# IRIO.net
KiCad netlist of a schematic drawn in EAGLE
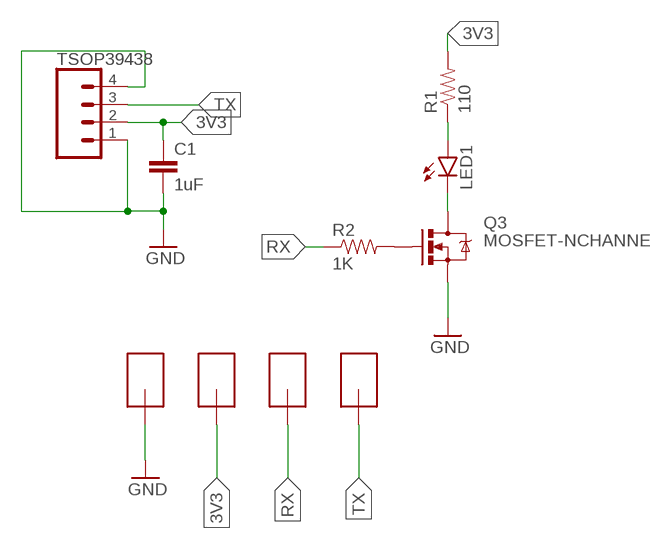
[diagram p0: schematic, sheet 1]

(export (version "E")
  (design (tool "Eeschema 10.0.6"))
  (components
    (comp (ref "C1")
      (value "1uF")
      (footprint "eagle-import:0805")
      (libsource (lib "eagle-import") (part "CAP0805"))
    )
    (comp (ref "LED1")
      (value "LED5MM")
      (footprint "eagle-import:LED5MM")
      (libsource (lib "eagle-import") (part "LED5MM"))
    )
    (comp (ref "Q3")
      (value "MOSFET-NCHANNEL")
      (footprint "eagle-import:SOT23-3")
      (libsource (lib "eagle-import") (part "MOSFET-NCHANNELAO3404A"))
    )
    (comp (ref "R1")
      (value "110")
      (footprint "eagle-import:0805")
      (libsource (lib "eagle-import") (part "RESISTOR0805-RES"))
    )
    (comp (ref "R2")
      (value "1K")
      (footprint "eagle-import:0805")
      (libsource (lib "eagle-import") (part "RESISTOR0805-RES"))
    )
    (comp (ref "TSOP39438")
      (value "CONN_041.27MM")
      (footprint "eagle-import:1X04_1.27MM")
      (libsource (lib "eagle-import") (part "CONN_041.27MM"))
    )
    (comp (ref "U$1")
      (value "SMD-PAD1SMD-PAD80X32")
      (footprint "eagle-import:SMD-PAD6")
      (libsource (lib "eagle-import") (part "SMD-PAD1SMD-PAD80X32"))
    )
    (comp (ref "U$2")
      (value "SMD-PAD1SMD-PAD80X32")
      (footprint "eagle-import:SMD-PAD6")
      (libsource (lib "eagle-import") (part "SMD-PAD1SMD-PAD80X32"))
    )
    (comp (ref "U$3")
      (value "SMD-PAD1SMD-PAD80X32")
      (footprint "eagle-import:SMD-PAD6")
      (libsource (lib "eagle-import") (part "SMD-PAD1SMD-PAD80X32"))
    )
    (comp (ref "U$4")
      (value "SMD-PAD1SMD-PAD80X32")
      (footprint "eagle-import:SMD-PAD6")
      (libsource (lib "eagle-import") (part "SMD-PAD1SMD-PAD80X32"))
    )
  )
  (nets
    (net (code "1") (name "3V3") (class "Default")
      (node (ref "C1") (pin "1") (pinfunction "1_1") (pintype "passive"))
      (node (ref "R1") (pin "2") (pinfunction "2_2") (pintype "passive"))
      (node (ref "TSOP39438") (pin "2") (pinfunction "2_2") (pintype "passive"))
      (node (ref "U$3") (pin ">PAD") (pinfunction "P$1_>PAD") (pintype "bidirectional"))
    )
    (net (code "2") (name "GND") (class "Default")
      (node (ref "C1") (pin "2") (pinfunction "2_2") (pintype "passive"))
      (node (ref "Q3") (pin "2") (pinfunction "S_2") (pintype "passive"))
      (node (ref "TSOP39438") (pin "1") (pinfunction "1_1") (pintype "passive"))
      (node (ref "TSOP39438") (pin "4") (pinfunction "4_4") (pintype "passive"))
      (node (ref "U$2") (pin ">PAD") (pinfunction "P$1_>PAD") (pintype "bidirectional"))
    )
    (net (code "3") (name "Net-(LED1-C)") (class "Default")
      (node (ref "LED1") (pin "K") (pinfunction "C_K") (pintype "passive"))
      (node (ref "Q3") (pin "3") (pinfunction "D_3") (pintype "passive"))
    )
    (net (code "4") (name "Net-(LED1-PadA)") (class "Default")
      (node (ref "LED1") (pin "A") (pinfunction "A_A") (pintype "passive"))
      (node (ref "R1") (pin "1") (pinfunction "1_1") (pintype "passive"))
    )
    (net (code "5") (name "Net-(Q3-G)") (class "Default")
      (node (ref "Q3") (pin "1") (pinfunction "G_1") (pintype "passive"))
      (node (ref "R2") (pin "2") (pinfunction "2_2") (pintype "passive"))
    )
    (net (code "6") (name "RX") (class "Default")
      (node (ref "R2") (pin "1") (pinfunction "1_1") (pintype "passive"))
      (node (ref "U$1") (pin ">PAD") (pinfunction "P$1_>PAD") (pintype "bidirectional"))
    )
    (net (code "7") (name "TX") (class "Default")
      (node (ref "TSOP39438") (pin "3") (pinfunction "3_3") (pintype "passive"))
      (node (ref "U$4") (pin ">PAD") (pinfunction "P$1_>PAD") (pintype "bidirectional"))
    )
  )
)
